# SCH_New_Project_2024-01-01.net
KiCad netlist of a schematic drawn in EasyEDA
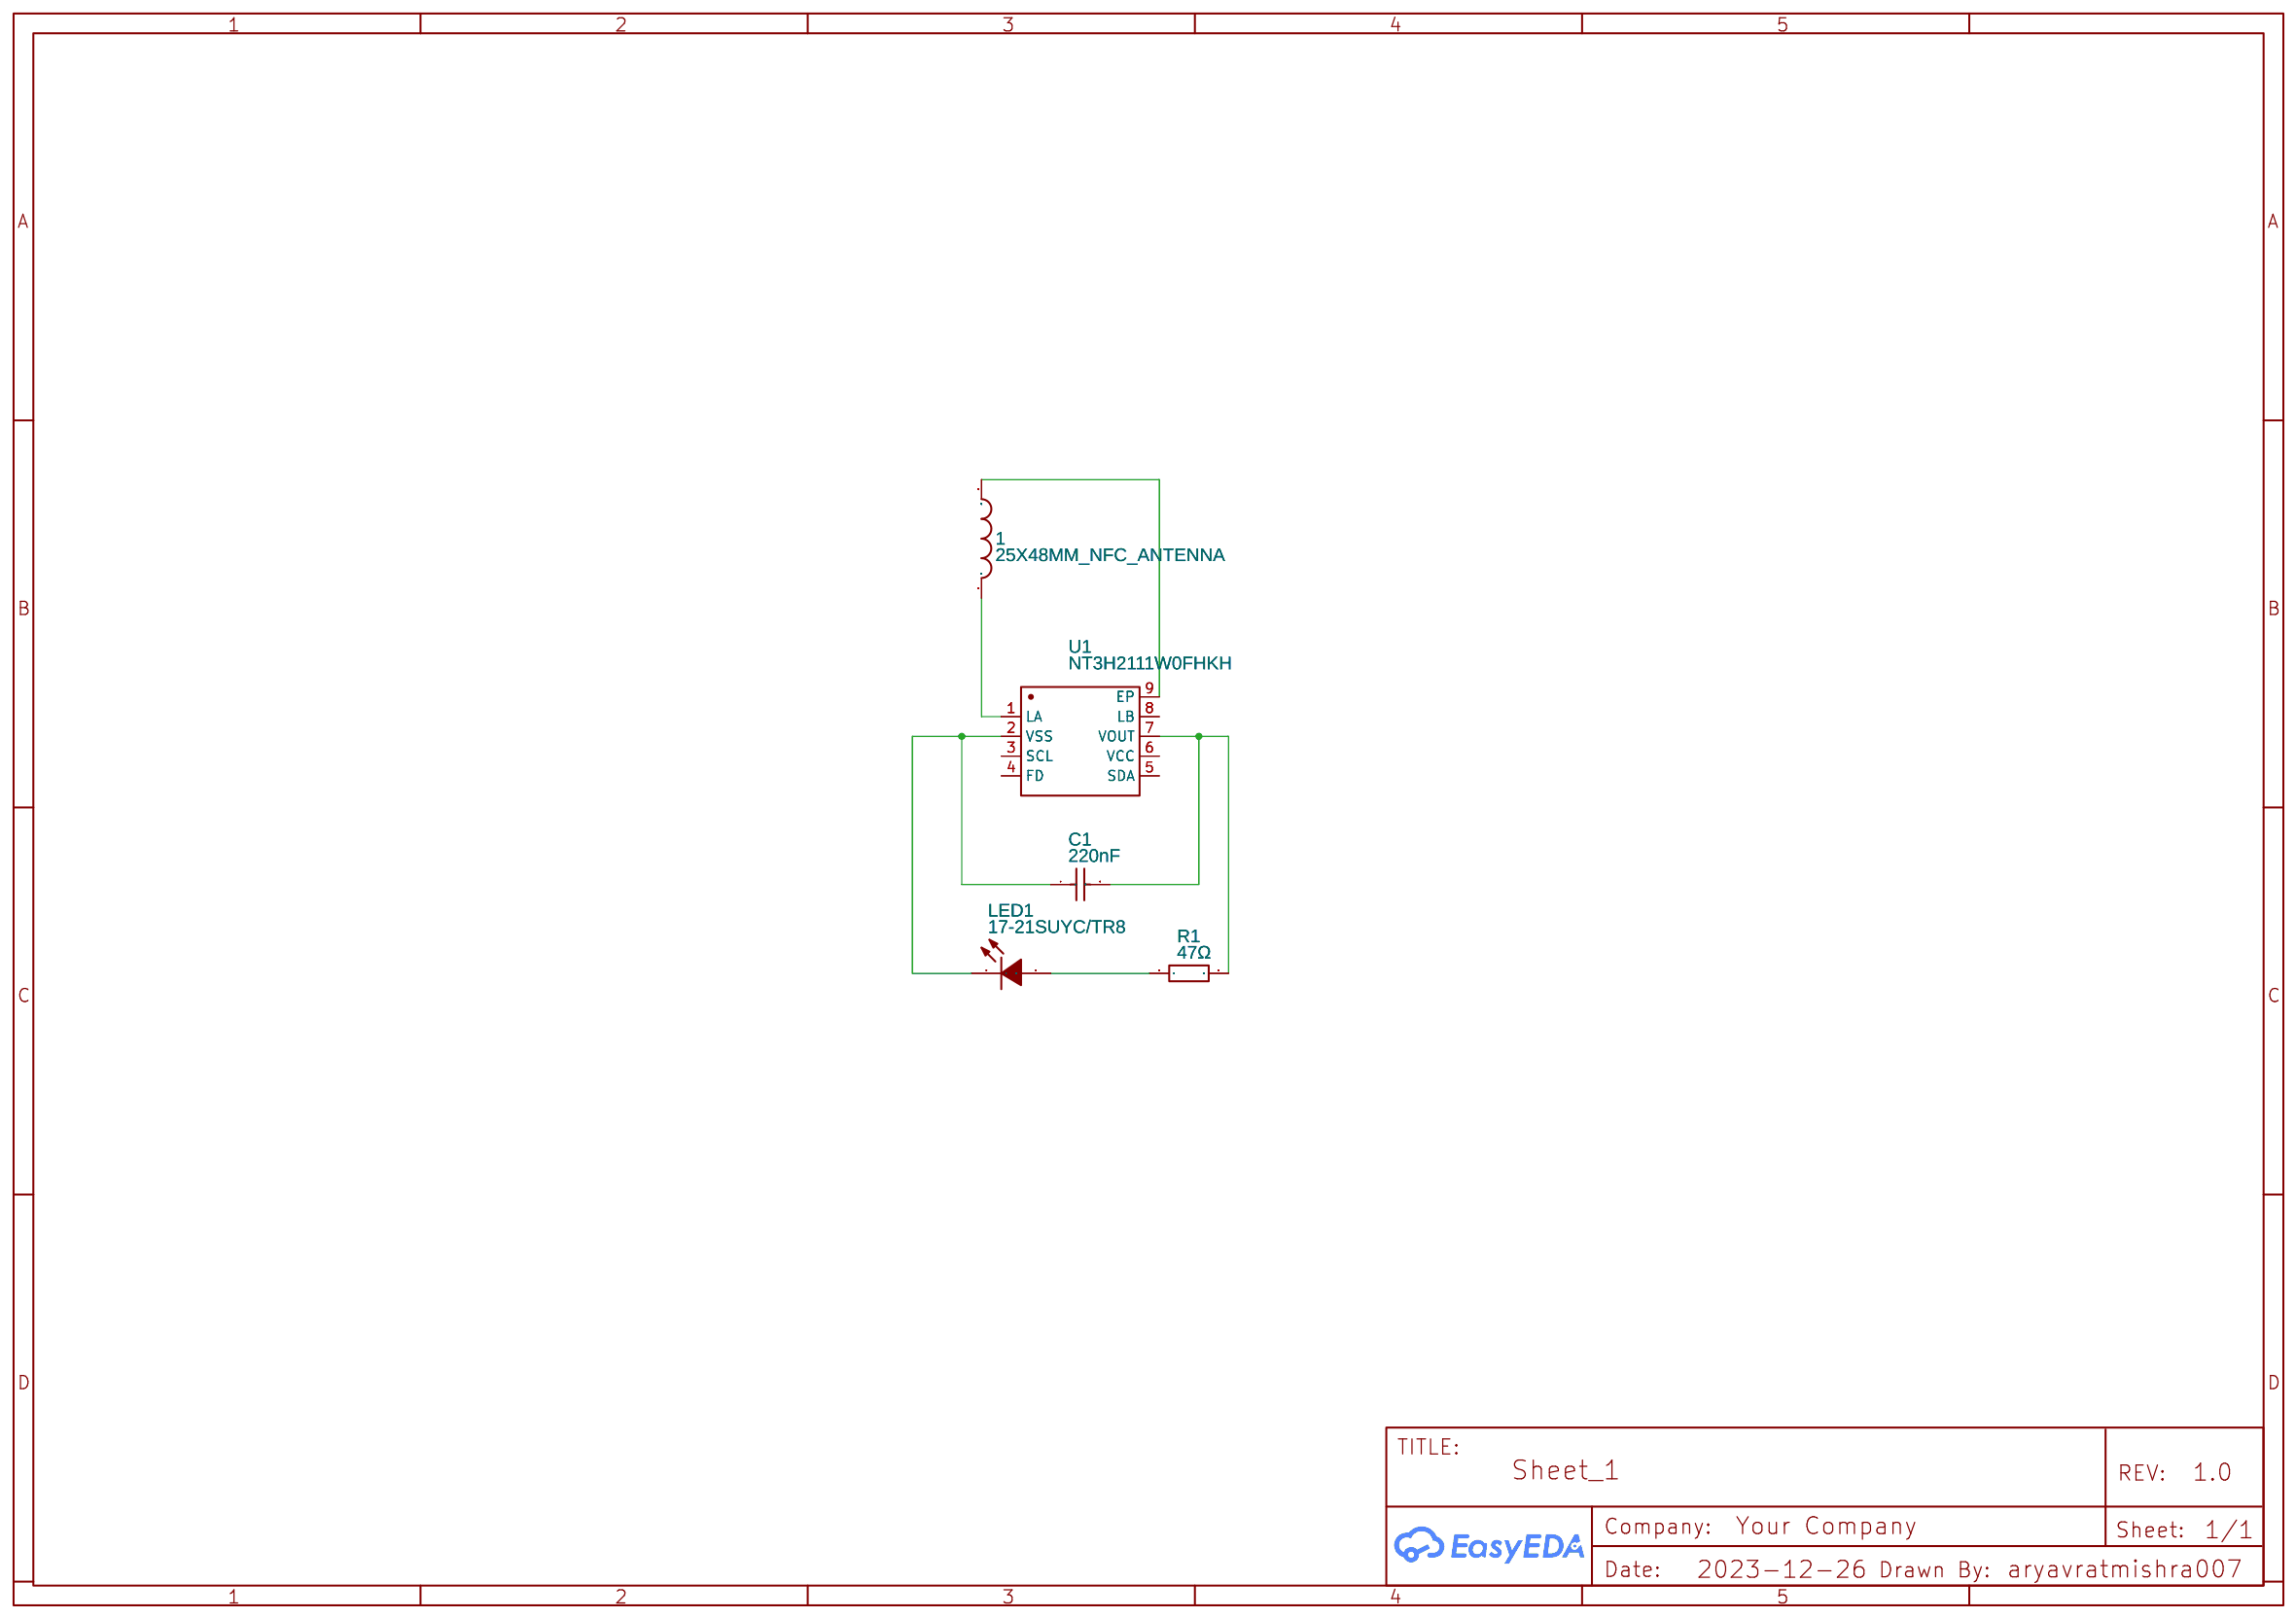
[diagram p0: schematic sheet]

(export (version "E")
  (design (tool "Eeschema 10.0.6"))
  (components
    (comp (ref "1") (value "25X48MM_NFC_ANTENNA") (libsource (lib "") (part "25X48MM_NFC_ANTENNA")))
    (comp (ref "C1")
      (value "220nF")
      (fields
        (field (name "Manufacturer Part") "CL10B224KA8NNNC")
        (field (name "Manufacturer") "SAMSUNG(三星)")
      )
      (libsource (lib "") (part "CL10B224KA8NNNC"))
    )
    (comp (ref "LED1")
      (value "17-21SUYC/TR8")
      (fields (field (name "Manufacturer Part") "KT-0805黄灯") (field (name "Manufacturer") "KENTO"))
      (libsource (lib "") (part "17-21SUYC/TR8"))
    )
    (comp (ref "R1")
      (value "47Ω")
      (fields
        (field (name "Manufacturer Part") "0603WAF470JT5E")
        (field (name "Manufacturer") "UNI-ROYAL(厚声)")
      )
      (libsource (lib "") (part "0603WAF470JT5E"))
    )
    (comp (ref "U1")
      (value "NT3H2111W0FHKH")
      (fields (field (name "Manufacturer") "NXP(恩智浦)"))
      (libsource (lib "") (part "NT3H2111W0FHKH"))
    )
  )
  (nets
    (net (code "1") (name "Net-(LED1-+)") (class "Default")
      (node (ref "LED1") (pin "1") (pinfunction "+_1") (pintype "unspecified"))
      (node (ref "R1") (pin "1") (pinfunction "1_1") (pintype "input"))
    )
    (net (code "2") (name "Net-(LED1--)") (class "Default")
      (node (ref "C1") (pin "1") (pinfunction "1_1") (pintype "input"))
      (node (ref "LED1") (pin "2") (pinfunction "-_2") (pintype "unspecified"))
      (node (ref "U1") (pin "2") (pinfunction "VSS_2") (pintype "unspecified"))
    )
    (net (code "3") (name "Net-(U1-EP)") (class "Default")
      (node (ref "1") (pin "P$1") (pinfunction "P$1_P$1") (pintype "bidirectional"))
      (node (ref "U1") (pin "9") (pinfunction "EP_9") (pintype "unspecified"))
    )
    (net (code "4") (name "Net-(U1-LA)") (class "Default")
      (node (ref "1") (pin "P$2") (pinfunction "P$2_P$2") (pintype "bidirectional"))
      (node (ref "U1") (pin "1") (pinfunction "LA_1") (pintype "unspecified"))
    )
    (net (code "5") (name "Net-(U1-VOUT)") (class "Default")
      (node (ref "C1") (pin "2") (pinfunction "2_2") (pintype "input"))
      (node (ref "R1") (pin "2") (pinfunction "2_2") (pintype "input"))
      (node (ref "U1") (pin "7") (pinfunction "VOUT_7") (pintype "unspecified"))
    )
    (net (code "6") (name "unconnected-(U1-FD-Pad4)") (class "Default")
      (node (ref "U1") (pin "4") (pinfunction "FD_4") (pintype "unspecified"))
    )
    (net (code "7") (name "unconnected-(U1-LB-Pad8)") (class "Default")
      (node (ref "U1") (pin "8") (pinfunction "LB_8") (pintype "unspecified"))
    )
    (net (code "8") (name "unconnected-(U1-SCL-Pad3)") (class "Default")
      (node (ref "U1") (pin "3") (pinfunction "SCL_3") (pintype "unspecified"))
    )
    (net (code "9") (name "unconnected-(U1-SDA-Pad5)") (class "Default")
      (node (ref "U1") (pin "5") (pinfunction "SDA_5") (pintype "unspecified"))
    )
    (net (code "10") (name "unconnected-(U1-VCC-Pad6)") (class "Default")
      (node (ref "U1") (pin "6") (pinfunction "VCC_6") (pintype "unspecified"))
    )
  )
)
